# cvsource.net
KiCad netlist of a schematic drawn in EAGLE
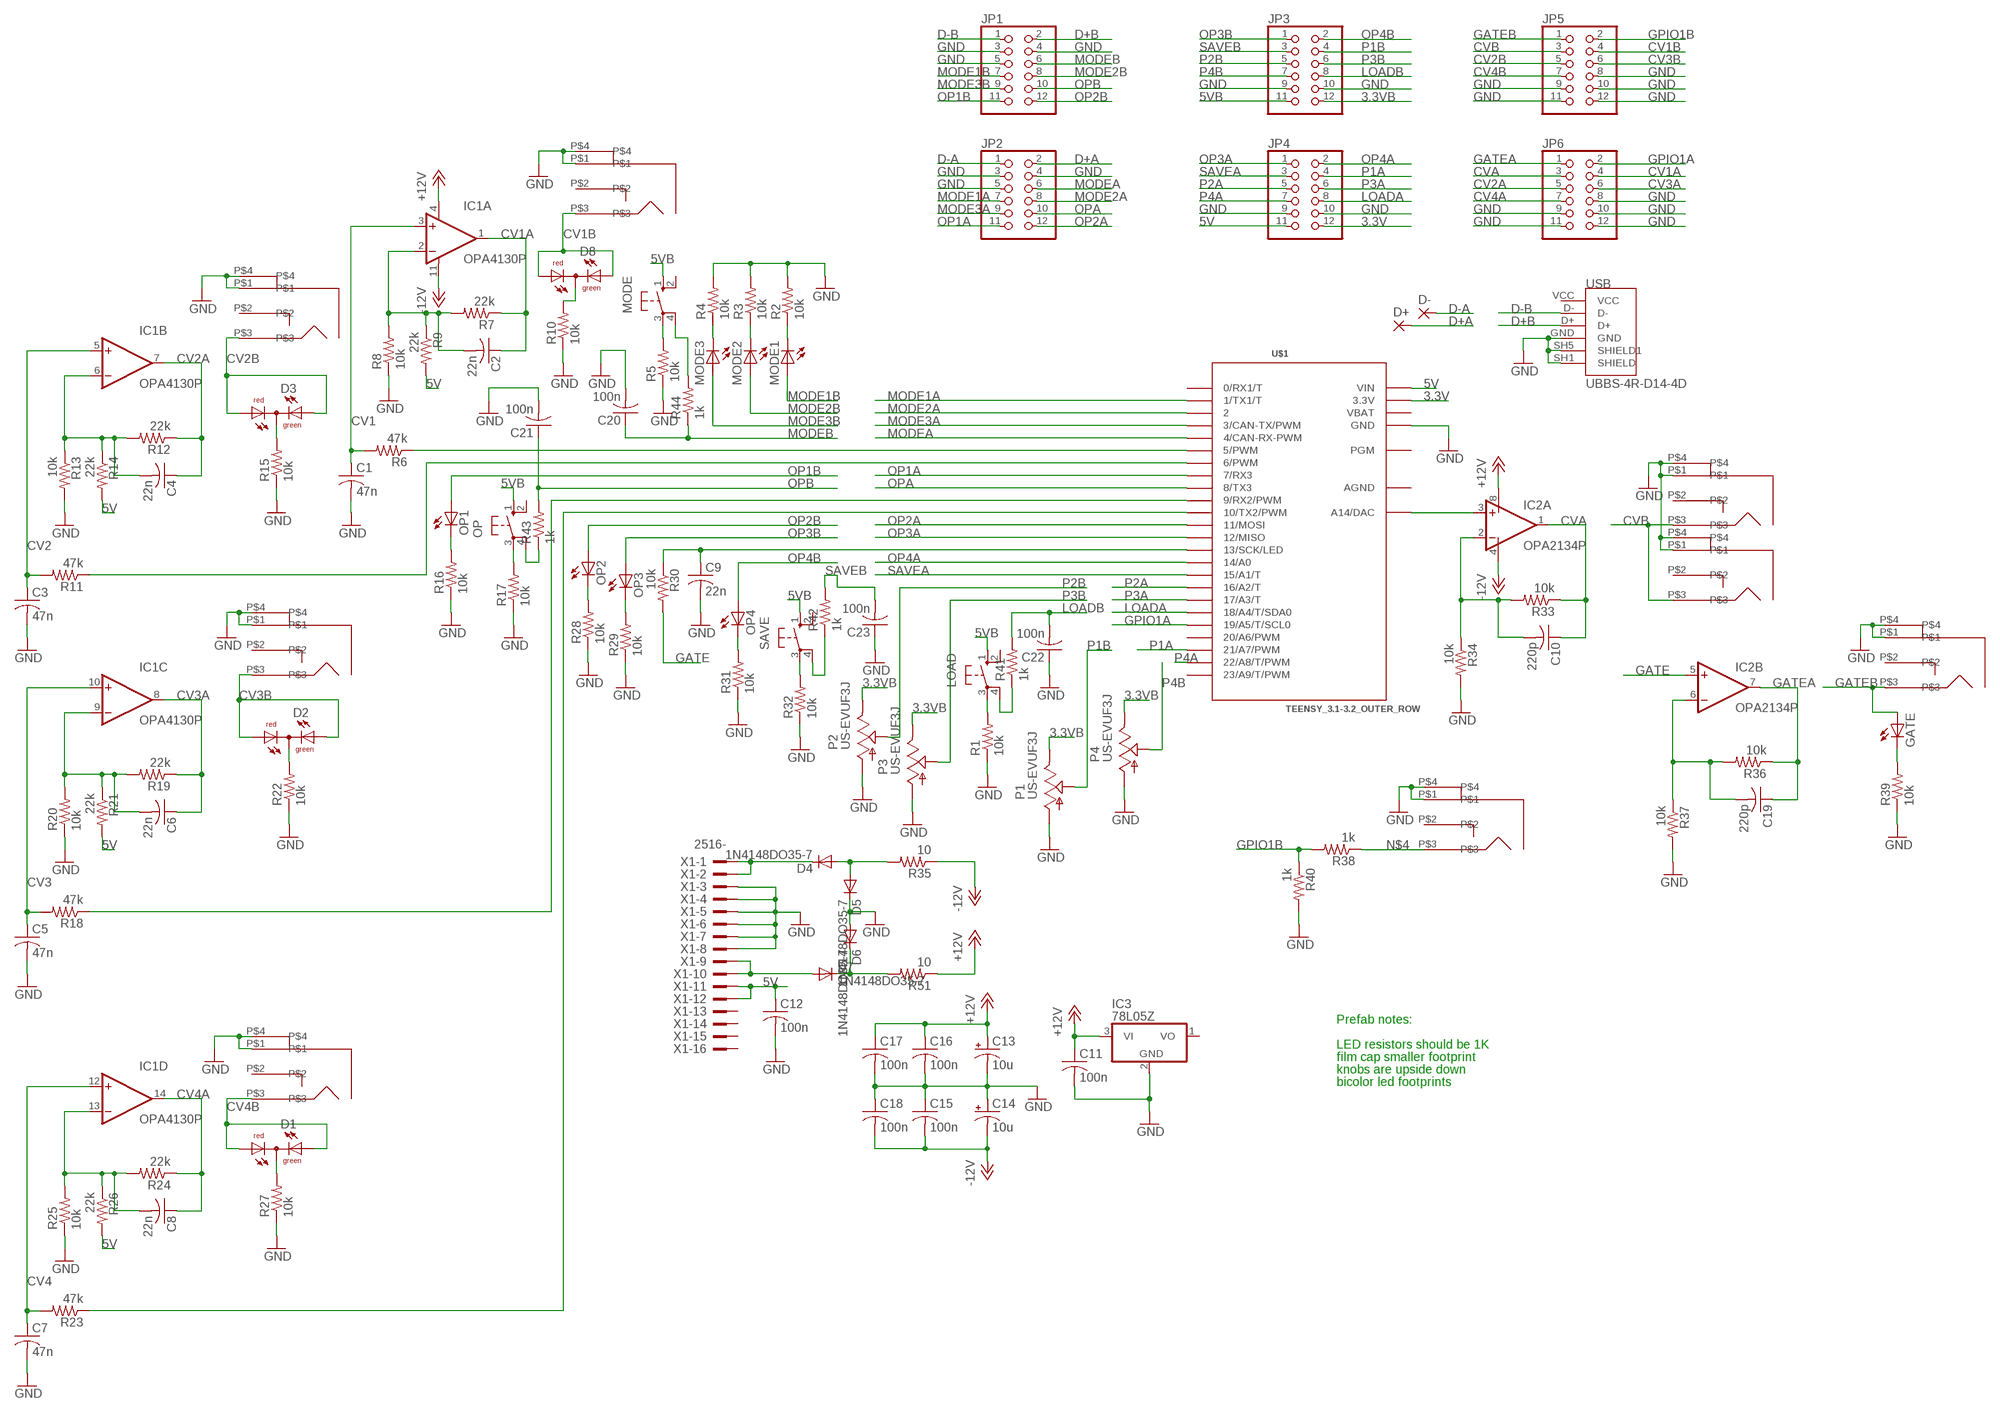
[diagram p0: schematic, sheet 1]

(export (version "E")
  (design (tool "Eeschema 10.0.6"))
  (components
    (comp (ref "C1")
      (value "47n")
      (footprint "eagle-import:C075-032X103")
      (libsource (lib "eagle-import") (part "C-US075-032X103"))
    )
    (comp (ref "C2")
      (value "22n")
      (footprint "eagle-import:C075-032X103")
      (libsource (lib "eagle-import") (part "C-US075-032X103"))
    )
    (comp (ref "C3")
      (value "47n")
      (footprint "eagle-import:C075-032X103")
      (libsource (lib "eagle-import") (part "C-US075-032X103"))
    )
    (comp (ref "C4")
      (value "22n")
      (footprint "eagle-import:C075-032X103")
      (libsource (lib "eagle-import") (part "C-US075-032X103"))
    )
    (comp (ref "C5")
      (value "47n")
      (footprint "eagle-import:C075-032X103")
      (libsource (lib "eagle-import") (part "C-US075-032X103"))
    )
    (comp (ref "C6")
      (value "22n")
      (footprint "eagle-import:C075-032X103")
      (libsource (lib "eagle-import") (part "C-US075-032X103"))
    )
    (comp (ref "C7")
      (value "47n")
      (footprint "eagle-import:C075-032X103")
      (libsource (lib "eagle-import") (part "C-US075-032X103"))
    )
    (comp (ref "C8")
      (value "22n")
      (footprint "eagle-import:C075-032X103")
      (libsource (lib "eagle-import") (part "C-US075-032X103"))
    )
    (comp (ref "C9")
      (value "22n")
      (footprint "eagle-import:C075-032X103")
      (libsource (lib "eagle-import") (part "C-US075-032X103"))
    )
    (comp (ref "C10")
      (value "220p")
      (footprint "eagle-import:C075-032X103")
      (libsource (lib "eagle-import") (part "C-US075-032X103"))
    )
    (comp (ref "C11")
      (value "100n")
      (footprint "eagle-import:C075-032X103")
      (libsource (lib "eagle-import") (part "C-US075-032X103"))
    )
    (comp (ref "C12")
      (value "100n")
      (footprint "eagle-import:C075-032X103")
      (libsource (lib "eagle-import") (part "C-US075-032X103"))
    )
    (comp (ref "C13")
      (value "10u")
      (footprint "eagle-import:E5-10,5")
      (libsource (lib "eagle-import") (part "CPOL-USE5-10.5"))
    )
    (comp (ref "C14")
      (value "10u")
      (footprint "eagle-import:E5-10,5")
      (libsource (lib "eagle-import") (part "CPOL-USE5-10.5"))
    )
    (comp (ref "C15")
      (value "100n")
      (footprint "eagle-import:C075-032X103")
      (libsource (lib "eagle-import") (part "C-US075-032X103"))
    )
    (comp (ref "C16")
      (value "100n")
      (footprint "eagle-import:C075-032X103")
      (libsource (lib "eagle-import") (part "C-US075-032X103"))
    )
    (comp (ref "C17")
      (value "100n")
      (footprint "eagle-import:C075-032X103")
      (libsource (lib "eagle-import") (part "C-US075-032X103"))
    )
    (comp (ref "C18")
      (value "100n")
      (footprint "eagle-import:C075-032X103")
      (libsource (lib "eagle-import") (part "C-US075-032X103"))
    )
    (comp (ref "C19")
      (value "220p")
      (footprint "eagle-import:C075-032X103")
      (libsource (lib "eagle-import") (part "C-US075-032X103"))
    )
    (comp (ref "C20")
      (value "100n")
      (footprint "eagle-import:C075-032X103")
      (libsource (lib "eagle-import") (part "C-US075-032X103"))
    )
    (comp (ref "C21")
      (value "100n")
      (footprint "eagle-import:C075-032X103")
      (libsource (lib "eagle-import") (part "C-US075-032X103"))
    )
    (comp (ref "C22")
      (value "100n")
      (footprint "eagle-import:C075-032X103")
      (libsource (lib "eagle-import") (part "C-US075-032X103"))
    )
    (comp (ref "C23")
      (value "100n")
      (footprint "eagle-import:C075-032X103")
      (libsource (lib "eagle-import") (part "C-US075-032X103"))
    )
    (comp (ref "CVOUT")
      (value "PJ301BM")
      (footprint "eagle-import:PJ301BM")
      (libsource (lib "eagle-import") (part "PJ301BM"))
    )
    (comp (ref "CVOUT1")
      (value "PJ301BM")
      (footprint "eagle-import:PJ301BM")
      (libsource (lib "eagle-import") (part "PJ301BM"))
    )
    (comp (ref "CVOUT2")
      (value "PJ301BM")
      (footprint "eagle-import:PJ301BM")
      (libsource (lib "eagle-import") (part "PJ301BM"))
    )
    (comp (ref "CVOUT3")
      (value "PJ301BM")
      (footprint "eagle-import:PJ301BM")
      (libsource (lib "eagle-import") (part "PJ301BM"))
    )
    (comp (ref "CVOUT4")
      (value "PJ301BM")
      (footprint "eagle-import:PJ301BM")
      (libsource (lib "eagle-import") (part "PJ301BM"))
    )
    (comp (ref "CVOUT5")
      (value "PJ301BM")
      (footprint "eagle-import:PJ301BM")
      (libsource (lib "eagle-import") (part "PJ301BM"))
    )
    (comp (ref "CVOUT6")
      (value "PJ301BM")
      (footprint "eagle-import:PJ301BM")
      (libsource (lib "eagle-import") (part "PJ301BM"))
    )
    (comp (ref "CVOUT7")
      (value "PJ301BM")
      (footprint "eagle-import:PJ301BM")
      (libsource (lib "eagle-import") (part "PJ301BM"))
    )
    (comp (ref "D+")
      (value "2,0/0,9-R")
      (footprint "eagle-import:2,0_0,9-R")
      (libsource (lib "eagle-import") (part "2,0/0,9-R"))
    )
    (comp (ref "D-")
      (value "2,0/0,9-R")
      (footprint "eagle-import:2,0_0,9-R")
      (libsource (lib "eagle-import") (part "2,0/0,9-R"))
    )
    (comp (ref "D1")
      (value "DUOLED5MM")
      (footprint "eagle-import:DUOLED5MM")
      (libsource (lib "eagle-import") (part "DUOLED5MM"))
    )
    (comp (ref "D2")
      (value "DUOLED5MM")
      (footprint "eagle-import:DUOLED5MM")
      (libsource (lib "eagle-import") (part "DUOLED5MM"))
    )
    (comp (ref "D3")
      (value "DUOLED5MM")
      (footprint "eagle-import:DUOLED5MM")
      (libsource (lib "eagle-import") (part "DUOLED5MM"))
    )
    (comp (ref "D4")
      (value "1N4148DO35-7")
      (footprint "eagle-import:DO35-7")
      (libsource (lib "eagle-import") (part "1N4148DO35-7"))
    )
    (comp (ref "D5")
      (value "1N4148DO35-7")
      (footprint "eagle-import:DO35-7")
      (libsource (lib "eagle-import") (part "1N4148DO35-7"))
    )
    (comp (ref "D6")
      (value "1N4148DO35-7")
      (footprint "eagle-import:DO35-7")
      (libsource (lib "eagle-import") (part "1N4148DO35-7"))
    )
    (comp (ref "D7")
      (value "1N4148DO35-7")
      (footprint "eagle-import:DO35-7")
      (libsource (lib "eagle-import") (part "1N4148DO35-7"))
    )
    (comp (ref "D8")
      (value "DUOLED5MM")
      (footprint "eagle-import:DUOLED5MM")
      (libsource (lib "eagle-import") (part "DUOLED5MM"))
    )
    (comp (ref "GATE")
      (value "LED5MM")
      (footprint "eagle-import:LED5MM")
      (libsource (lib "eagle-import") (part "LED5MM"))
    )
    (comp (ref "IC1")
      (value "OPA4130P")
      (footprint "eagle-import:DIL14")
      (libsource (lib "eagle-import") (part "OPA4130P"))
    )
    (comp (ref "IC2")
      (value "OPA2134P")
      (footprint "eagle-import:DIL08")
      (libsource (lib "eagle-import") (part "OPA2134P"))
    )
    (comp (ref "IC3")
      (value "78L05Z")
      (footprint "eagle-import:TO92")
      (libsource (lib "eagle-import") (part "78ZL05"))
    )
    (comp (ref "JP1")
      (value "PINHD-2X6")
      (footprint "eagle-import:2X06")
      (libsource (lib "eagle-import") (part "PINHD-2X6"))
    )
    (comp (ref "JP2")
      (value "PINHD-2X6")
      (footprint "eagle-import:2X06")
      (libsource (lib "eagle-import") (part "PINHD-2X6"))
    )
    (comp (ref "JP3")
      (value "PINHD-2X6")
      (footprint "eagle-import:2X06")
      (libsource (lib "eagle-import") (part "PINHD-2X6"))
    )
    (comp (ref "JP4")
      (value "PINHD-2X6")
      (footprint "eagle-import:2X06")
      (libsource (lib "eagle-import") (part "PINHD-2X6"))
    )
    (comp (ref "JP5")
      (value "PINHD-2X6")
      (footprint "eagle-import:2X06")
      (libsource (lib "eagle-import") (part "PINHD-2X6"))
    )
    (comp (ref "JP6")
      (value "PINHD-2X6")
      (footprint "eagle-import:2X06")
      (libsource (lib "eagle-import") (part "PINHD-2X6"))
    )
    (comp (ref "LOAD")
      (value "40-XX")
      (footprint "eagle-import:B3F-40XX")
      (fields (field (name "MF") "OMRON COMPONENTS USA") (field (name "MPN") "B3F-4000"))
      (libsource (lib "eagle-import") (part "40-XX"))
    )
    (comp (ref "MODE")
      (value "40-XX")
      (footprint "eagle-import:B3F-40XX")
      (fields (field (name "MF") "OMRON COMPONENTS USA") (field (name "MPN") "B3F-4000"))
      (libsource (lib "eagle-import") (part "40-XX"))
    )
    (comp (ref "MODE1")
      (value "LED5MM")
      (footprint "eagle-import:LED5MM")
      (libsource (lib "eagle-import") (part "LED5MM"))
    )
    (comp (ref "MODE2")
      (value "LED5MM")
      (footprint "eagle-import:LED5MM")
      (libsource (lib "eagle-import") (part "LED5MM"))
    )
    (comp (ref "MODE3")
      (value "LED5MM")
      (footprint "eagle-import:LED5MM")
      (libsource (lib "eagle-import") (part "LED5MM"))
    )
    (comp (ref "OP")
      (value "40-XX")
      (footprint "eagle-import:B3F-40XX")
      (fields (field (name "MF") "OMRON COMPONENTS USA") (field (name "MPN") "B3F-4000"))
      (libsource (lib "eagle-import") (part "40-XX"))
    )
    (comp (ref "OP1")
      (value "LED5MM")
      (footprint "eagle-import:LED5MM")
      (libsource (lib "eagle-import") (part "LED5MM"))
    )
    (comp (ref "OP2")
      (value "LED5MM")
      (footprint "eagle-import:LED5MM")
      (libsource (lib "eagle-import") (part "LED5MM"))
    )
    (comp (ref "OP3")
      (value "LED5MM")
      (footprint "eagle-import:LED5MM")
      (libsource (lib "eagle-import") (part "LED5MM"))
    )
    (comp (ref "OP4")
      (value "LED5MM")
      (footprint "eagle-import:LED5MM")
      (libsource (lib "eagle-import") (part "LED5MM"))
    )
    (comp (ref "P1")
      (value "US-EVUF3J")
      (footprint "eagle-import:EVUFXJ")
      (libsource (lib "eagle-import") (part "US-EVUF3J"))
    )
    (comp (ref "P2")
      (value "US-EVUF3J")
      (footprint "eagle-import:EVUFXJ")
      (libsource (lib "eagle-import") (part "US-EVUF3J"))
    )
    (comp (ref "P3")
      (value "US-EVUF3J")
      (footprint "eagle-import:EVUFXJ")
      (libsource (lib "eagle-import") (part "US-EVUF3J"))
    )
    (comp (ref "P4")
      (value "US-EVUF3J")
      (footprint "eagle-import:EVUFXJ")
      (libsource (lib "eagle-import") (part "US-EVUF3J"))
    )
    (comp (ref "R1")
      (value "10k")
      (footprint "eagle-import:0207_2V")
      (libsource (lib "eagle-import") (part "R-US_0207/2V"))
    )
    (comp (ref "R2")
      (value "10k")
      (footprint "eagle-import:0207_2V")
      (libsource (lib "eagle-import") (part "R-US_0207/2V"))
    )
    (comp (ref "R3")
      (value "10k")
      (footprint "eagle-import:0207_2V")
      (libsource (lib "eagle-import") (part "R-US_0207/2V"))
    )
    (comp (ref "R4")
      (value "10k")
      (footprint "eagle-import:0207_2V")
      (libsource (lib "eagle-import") (part "R-US_0207/2V"))
    )
    (comp (ref "R5")
      (value "10k")
      (footprint "eagle-import:0207_2V")
      (libsource (lib "eagle-import") (part "R-US_0207/2V"))
    )
    (comp (ref "R6")
      (value "47k")
      (footprint "eagle-import:0207_2V")
      (libsource (lib "eagle-import") (part "R-US_0207/2V"))
    )
    (comp (ref "R7")
      (value "22k")
      (footprint "eagle-import:0207_2V")
      (libsource (lib "eagle-import") (part "R-US_0207/2V"))
    )
    (comp (ref "R8")
      (value "10k")
      (footprint "eagle-import:0207_2V")
      (libsource (lib "eagle-import") (part "R-US_0207/2V"))
    )
    (comp (ref "R9")
      (value "22k")
      (footprint "eagle-import:0207_2V")
      (libsource (lib "eagle-import") (part "R-US_0207/2V"))
    )
    (comp (ref "R10")
      (value "10k")
      (footprint "eagle-import:0207_2V")
      (libsource (lib "eagle-import") (part "R-US_0207/2V"))
    )
    (comp (ref "R11")
      (value "47k")
      (footprint "eagle-import:0207_2V")
      (libsource (lib "eagle-import") (part "R-US_0207/2V"))
    )
    (comp (ref "R12")
      (value "22k")
      (footprint "eagle-import:0207_2V")
      (libsource (lib "eagle-import") (part "R-US_0207/2V"))
    )
    (comp (ref "R13")
      (value "10k")
      (footprint "eagle-import:0207_2V")
      (libsource (lib "eagle-import") (part "R-US_0207/2V"))
    )
    (comp (ref "R14")
      (value "22k")
      (footprint "eagle-import:0207_2V")
      (libsource (lib "eagle-import") (part "R-US_0207/2V"))
    )
    (comp (ref "R15")
      (value "10k")
      (footprint "eagle-import:0207_2V")
      (libsource (lib "eagle-import") (part "R-US_0207/2V"))
    )
    (comp (ref "R16")
      (value "10k")
      (footprint "eagle-import:0207_2V")
      (libsource (lib "eagle-import") (part "R-US_0207/2V"))
    )
    (comp (ref "R17")
      (value "10k")
      (footprint "eagle-import:0207_2V")
      (libsource (lib "eagle-import") (part "R-US_0207/2V"))
    )
    (comp (ref "R18")
      (value "47k")
      (footprint "eagle-import:0207_2V")
      (libsource (lib "eagle-import") (part "R-US_0207/2V"))
    )
    (comp (ref "R19")
      (value "22k")
      (footprint "eagle-import:0207_2V")
      (libsource (lib "eagle-import") (part "R-US_0207/2V"))
    )
    (comp (ref "R20")
      (value "10k")
      (footprint "eagle-import:0207_2V")
      (libsource (lib "eagle-import") (part "R-US_0207/2V"))
    )
    (comp (ref "R21")
      (value "22k")
      (footprint "eagle-import:0207_2V")
      (libsource (lib "eagle-import") (part "R-US_0207/2V"))
    )
    (comp (ref "R22")
      (value "10k")
      (footprint "eagle-import:0207_2V")
      (libsource (lib "eagle-import") (part "R-US_0207/2V"))
    )
    (comp (ref "R23")
      (value "47k")
      (footprint "eagle-import:0207_2V")
      (libsource (lib "eagle-import") (part "R-US_0207/2V"))
    )
    (comp (ref "R24")
      (value "22k")
      (footprint "eagle-import:0207_2V")
      (libsource (lib "eagle-import") (part "R-US_0207/2V"))
    )
    (comp (ref "R25")
      (value "10k")
      (footprint "eagle-import:0207_2V")
      (libsource (lib "eagle-import") (part "R-US_0207/2V"))
    )
    (comp (ref "R26")
      (value "22k")
      (footprint "eagle-import:0207_2V")
      (libsource (lib "eagle-import") (part "R-US_0207/2V"))
    )
    (comp (ref "R27")
      (value "10k")
      (footprint "eagle-import:0207_2V")
      (libsource (lib "eagle-import") (part "R-US_0207/2V"))
    )
    (comp (ref "R28")
      (value "10k")
      (footprint "eagle-import:0207_2V")
      (libsource (lib "eagle-import") (part "R-US_0207/2V"))
    )
    (comp (ref "R29")
      (value "10k")
      (footprint "eagle-import:0207_2V")
      (libsource (lib "eagle-import") (part "R-US_0207/2V"))
    )
    (comp (ref "R30")
      (value "10k")
      (footprint "eagle-import:0207_2V")
      (libsource (lib "eagle-import") (part "R-US_0207/2V"))
    )
    (comp (ref "R31")
      (value "10k")
      (footprint "eagle-import:0207_2V")
      (libsource (lib "eagle-import") (part "R-US_0207/2V"))
    )
    (comp (ref "R32")
      (value "10k")
      (footprint "eagle-import:0207_2V")
      (libsource (lib "eagle-import") (part "R-US_0207/2V"))
    )
    (comp (ref "R33")
      (value "10k")
      (footprint "eagle-import:0207_2V")
      (libsource (lib "eagle-import") (part "R-US_0207/2V"))
    )
    (comp (ref "R34")
      (value "10k")
      (footprint "eagle-import:0207_2V")
      (libsource (lib "eagle-import") (part "R-US_0207/2V"))
    )
    (comp (ref "R35")
      (value "10")
      (footprint "eagle-import:0207_2V")
      (libsource (lib "eagle-import") (part "R-US_0207/2V"))
    )
    (comp (ref "R36")
      (value "10k")
      (footprint "eagle-import:0207_2V")
      (libsource (lib "eagle-import") (part "R-US_0207/2V"))
    )
    (comp (ref "R37")
      (value "10k")
      (footprint "eagle-import:0207_2V")
      (libsource (lib "eagle-import") (part "R-US_0207/2V"))
    )
    (comp (ref "R38")
      (value "1k")
      (footprint "eagle-import:0207_2V")
      (libsource (lib "eagle-import") (part "R-US_0207/2V"))
    )
    (comp (ref "R39")
      (value "10k")
      (footprint "eagle-import:0207_2V")
      (libsource (lib "eagle-import") (part "R-US_0207/2V"))
    )
    (comp (ref "R40")
      (value "1k")
      (footprint "eagle-import:0207_2V")
      (libsource (lib "eagle-import") (part "R-US_0207/2V"))
    )
    (comp (ref "R41")
      (value "1k")
      (footprint "eagle-import:0207_2V")
      (libsource (lib "eagle-import") (part "R-US_0207/2V"))
    )
    (comp (ref "R42")
      (value "1k")
      (footprint "eagle-import:0207_2V")
      (libsource (lib "eagle-import") (part "R-US_0207/2V"))
    )
    (comp (ref "R43")
      (value "1k")
      (footprint "eagle-import:0207_2V")
      (libsource (lib "eagle-import") (part "R-US_0207/2V"))
    )
    (comp (ref "R44")
      (value "1k")
      (footprint "eagle-import:0207_2V")
      (libsource (lib "eagle-import") (part "R-US_0207/2V"))
    )
    (comp (ref "R51")
      (value "10")
      (footprint "eagle-import:0207_2V")
      (libsource (lib "eagle-import") (part "R-US_0207/2V"))
    )
    (comp (ref "SAVE")
      (value "40-XX")
      (footprint "eagle-import:B3F-40XX")
      (fields (field (name "MF") "OMRON COMPONENTS USA") (field (name "MPN") "B3F-4000"))
      (libsource (lib "eagle-import") (part "40-XX"))
    )
    (comp (ref "U$1")
      (value "TEENSY_3.1-3.2_OUTER_ROW")
      (footprint "eagle-import:TEENSY_3.0-3.2&LC_OUTER_ROW")
      (libsource (lib "eagle-import") (part "TEENSY_3.1-3.2_OUTER_ROW"))
    )
    (comp (ref "USB")
      (value "UBBS-4R-D14-4D")
      (footprint "eagle-import:JST_UBBS-4R-D14-4D")
      (fields (field (name "MF") "JST"))
      (libsource (lib "eagle-import") (part "UBBS-4R-D14-4D"))
    )
    (comp (ref "X1")
      (value "2516-")
      (footprint "eagle-import:PAK100_2500-16")
      (libsource (lib "eagle-import") (part "2516-"))
    )
  )
  (nets
    (net (code "1") (name "+12V") (class "Default")
      (node (ref "C11") (pin "1") (pinfunction "1_1") (pintype "passive"))
      (node (ref "C13") (pin "+") (pinfunction "+_+") (pintype "passive"))
      (node (ref "C16") (pin "1") (pinfunction "1_1") (pintype "passive"))
      (node (ref "C17") (pin "1") (pinfunction "1_1") (pintype "passive"))
      (node (ref "IC1") (pin "4") (pinfunction "V+_4") (pintype "power_in"))
      (node (ref "IC2") (pin "8") (pinfunction "V+_8") (pintype "power_in"))
      (node (ref "IC3") (pin "3") (pinfunction "VI_3") (pintype "input"))
      (node (ref "R51") (pin "1") (pinfunction "1_1") (pintype "passive"))
    )
    (net (code "2") (name "-12V") (class "Default")
      (node (ref "C14") (pin "-") (pinfunction "-_-") (pintype "passive"))
      (node (ref "C15") (pin "2") (pinfunction "2_2") (pintype "passive"))
      (node (ref "C18") (pin "2") (pinfunction "2_2") (pintype "passive"))
      (node (ref "IC1") (pin "11") (pinfunction "V-_11") (pintype "power_in"))
      (node (ref "IC2") (pin "4") (pinfunction "V-_4") (pintype "power_in"))
      (node (ref "R35") (pin "1") (pinfunction "1_1") (pintype "passive"))
    )
    (net (code "3") (name "/3.3V") (class "Default")
      (node (ref "JP4") (pin "12") (pinfunction "12_12") (pintype "passive"))
      (node (ref "U$1") (pin "3.3V") (pinfunction "3.3V_3.3V") (pintype "power_in"))
      (node (ref "U$1") (pin "3.3V1") (pinfunction "3.3V_3.3V1") (pintype "power_in"))
    )
    (net (code "4") (name "/3.3VB") (class "Default")
      (node (ref "JP3") (pin "12") (pinfunction "12_12") (pintype "passive"))
      (node (ref "P1") (pin "3") (pinfunction "E_3") (pintype "passive"))
      (node (ref "P2") (pin "3") (pinfunction "E_3") (pintype "passive"))
      (node (ref "P3") (pin "3") (pinfunction "E_3") (pintype "passive"))
      (node (ref "P4") (pin "3") (pinfunction "E_3") (pintype "passive"))
    )
    (net (code "5") (name "/5V") (class "Default")
      (node (ref "C12") (pin "1") (pinfunction "1_1") (pintype "passive"))
      (node (ref "JP4") (pin "11") (pinfunction "11_11") (pintype "passive"))
      (node (ref "R14") (pin "2") (pinfunction "2_2") (pintype "passive"))
      (node (ref "R21") (pin "2") (pinfunction "2_2") (pintype "passive"))
      (node (ref "R26") (pin "2") (pinfunction "2_2") (pintype "passive"))
      (node (ref "R9") (pin "2") (pinfunction "2_2") (pintype "passive"))
      (node (ref "U$1") (pin "VIN") (pinfunction "VIN_VIN") (pintype "power_in"))
      (node (ref "X1") (pin "11") (pinfunction "KL_11") (pintype "passive"))
      (node (ref "X1") (pin "12") (pinfunction "KL_12") (pintype "passive"))
    )
    (net (code "6") (name "/5VB") (class "Default")
      (node (ref "JP3") (pin "11") (pinfunction "11_11") (pintype "passive"))
      (node (ref "LOAD") (pin "1") (pinfunction "S_1") (pintype "passive"))
      (node (ref "MODE") (pin "1") (pinfunction "S_1") (pintype "passive"))
      (node (ref "OP") (pin "1") (pinfunction "S_1") (pintype "passive"))
      (node (ref "SAVE") (pin "1") (pinfunction "S_1") (pintype "passive"))
    )
    (net (code "7") (name "/AGND") (class "Default")
      (node (ref "U$1") (pin "AGND") (pinfunction "AGND_AGND") (pintype "power_in"))
    )
    (net (code "8") (name "/CV1") (class "Default")
      (node (ref "C1") (pin "1") (pinfunction "1_1") (pintype "passive"))
      (node (ref "IC1") (pin "3") (pinfunction "+IN_3") (pintype "input"))
      (node (ref "R6") (pin "2") (pinfunction "2_2") (pintype "passive"))
    )
    (net (code "9") (name "/CV1A") (class "Default")
      (node (ref "C2") (pin "1") (pinfunction "1_1") (pintype "passive"))
      (node (ref "IC1") (pin "1") (pinfunction "OUT_1") (pintype "output"))
      (node (ref "JP6") (pin "4") (pinfunction "4_4") (pintype "passive"))
      (node (ref "R7") (pin "1") (pinfunction "1_1") (pintype "passive"))
    )
    (net (code "10") (name "/CV1B") (class "Default")
      (node (ref "CVOUT1") (pin "P$3") (pinfunction "P$3_P$3") (pintype "bidirectional"))
      (node (ref "D8") (pin "AG") (pinfunction "AG_AG") (pintype "passive"))
      (node (ref "D8") (pin "AR") (pinfunction "AR_AR") (pintype "passive"))
      (node (ref "JP5") (pin "4") (pinfunction "4_4") (pintype "passive"))
    )
    (net (code "11") (name "/CV2") (class "Default")
      (node (ref "C3") (pin "1") (pinfunction "1_1") (pintype "passive"))
      (node (ref "IC1") (pin "5") (pinfunction "+IN_5") (pintype "input"))
      (node (ref "R11") (pin "2") (pinfunction "2_2") (pintype "passive"))
    )
    (net (code "12") (name "/CV2A") (class "Default")
      (node (ref "C4") (pin "1") (pinfunction "1_1") (pintype "passive"))
      (node (ref "IC1") (pin "7") (pinfunction "OUT_7") (pintype "output"))
      (node (ref "JP6") (pin "5") (pinfunction "5_5") (pintype "passive"))
      (node (ref "R12") (pin "1") (pinfunction "1_1") (pintype "passive"))
    )
    (net (code "13") (name "/CV2B") (class "Default")
      (node (ref "CVOUT2") (pin "P$3") (pinfunction "P$3_P$3") (pintype "bidirectional"))
      (node (ref "D3") (pin "AG") (pinfunction "AG_AG") (pintype "passive"))
      (node (ref "D3") (pin "AR") (pinfunction "AR_AR") (pintype "passive"))
      (node (ref "JP5") (pin "5") (pinfunction "5_5") (pintype "passive"))
    )
    (net (code "14") (name "/CV3") (class "Default")
      (node (ref "C5") (pin "1") (pinfunction "1_1") (pintype "passive"))
      (node (ref "IC1") (pin "10") (pinfunction "+IN_10") (pintype "input"))
      (node (ref "R18") (pin "2") (pinfunction "2_2") (pintype "passive"))
    )
    (net (code "15") (name "/CV3A") (class "Default")
      (node (ref "C6") (pin "1") (pinfunction "1_1") (pintype "passive"))
      (node (ref "IC1") (pin "8") (pinfunction "OUT_8") (pintype "output"))
      (node (ref "JP6") (pin "6") (pinfunction "6_6") (pintype "passive"))
      (node (ref "R19") (pin "1") (pinfunction "1_1") (pintype "passive"))
    )
    (net (code "16") (name "/CV3B") (class "Default")
      (node (ref "CVOUT3") (pin "P$3") (pinfunction "P$3_P$3") (pintype "bidirectional"))
      (node (ref "D2") (pin "AG") (pinfunction "AG_AG") (pintype "passive"))
      (node (ref "D2") (pin "AR") (pinfunction "AR_AR") (pintype "passive"))
      (node (ref "JP5") (pin "6") (pinfunction "6_6") (pintype "passive"))
    )
    (net (code "17") (name "/CV4") (class "Default")
      (node (ref "C7") (pin "1") (pinfunction "1_1") (pintype "passive"))
      (node (ref "IC1") (pin "12") (pinfunction "+IN_12") (pintype "input"))
      (node (ref "R23") (pin "2") (pinfunction "2_2") (pintype "passive"))
    )
    (net (code "18") (name "/CV4A") (class "Default")
      (node (ref "C8") (pin "1") (pinfunction "1_1") (pintype "passive"))
      (node (ref "IC1") (pin "14") (pinfunction "OUT_14") (pintype "output"))
      (node (ref "JP6") (pin "7") (pinfunction "7_7") (pintype "passive"))
      (node (ref "R24") (pin "1") (pinfunction "1_1") (pintype "passive"))
    )
    (net (code "19") (name "/CV4B") (class "Default")
      (node (ref "CVOUT4") (pin "P$3") (pinfunction "P$3_P$3") (pintype "bidirectional"))
      (node (ref "D1") (pin "AG") (pinfunction "AG_AG") (pintype "passive"))
      (node (ref "D1") (pin "AR") (pinfunction "AR_AR") (pintype "passive"))
      (node (ref "JP5") (pin "7") (pinfunction "7_7") (pintype "passive"))
    )
    (net (code "20") (name "/CVA") (class "Default")
      (node (ref "C10") (pin "1") (pinfunction "1_1") (pintype "passive"))
      (node (ref "IC2") (pin "1") (pinfunction "OUT_1") (pintype "output"))
      (node (ref "JP6") (pin "3") (pinfunction "3_3") (pintype "passive"))
      (node (ref "R33") (pin "1") (pinfunction "1_1") (pintype "passive"))
    )
    (net (code "21") (name "/CVB") (class "Default")
      (node (ref "CVOUT") (pin "P$3") (pinfunction "P$3_P$3") (pintype "bidirectional"))
      (node (ref "CVOUT6") (pin "P$3") (pinfunction "P$3_P$3") (pintype "bidirectional"))
      (node (ref "JP5") (pin "3") (pinfunction "3_3") (pintype "passive"))
    )
    (net (code "22") (name "/D+A") (class "Default")
      (node (ref "D+") (pin "1") (pinfunction "P_1") (pintype "passive"))
      (node (ref "JP2") (pin "2") (pinfunction "2_2") (pintype "passive"))
    )
    (net (code "23") (name "/D+B") (class "Default")
      (node (ref "JP1") (pin "2") (pinfunction "2_2") (pintype "passive"))
      (node (ref "USB") (pin "D+") (pinfunction "D+_D+") (pintype "passive"))
    )
    (net (code "24") (name "/D-A") (class "Default")
      (node (ref "D-") (pin "1") (pinfunction "P_1") (pintype "passive"))
      (node (ref "JP2") (pin "1") (pinfunction "1_1") (pintype "passive"))
    )
    (net (code "25") (name "/D-B") (class "Default")
      (node (ref "JP1") (pin "1") (pinfunction "1_1") (pintype "passive"))
      (node (ref "USB") (pin "D-") (pinfunction "D-_D-") (pintype "passive"))
    )
    (net (code "26") (name "/GATE") (class "Default")
      (node (ref "IC2") (pin "5") (pinfunction "+IN_5") (pintype "input"))
      (node (ref "R30") (pin "2") (pinfunction "2_2") (pintype "passive"))
    )
    (net (code "27") (name "/GATEA") (class "Default")
      (node (ref "C19") (pin "1") (pinfunction "1_1") (pintype "passive"))
      (node (ref "IC2") (pin "7") (pinfunction "OUT_7") (pintype "output"))
      (node (ref "JP6") (pin "1") (pinfunction "1_1") (pintype "passive"))
      (node (ref "R36") (pin "1") (pinfunction "1_1") (pintype "passive"))
    )
    (net (code "28") (name "/GATEB") (class "Default")
      (node (ref "CVOUT5") (pin "P$3") (pinfunction "P$3_P$3") (pintype "bidirectional"))
      (node (ref "GATE") (pin "A") (pinfunction "A_A") (pintype "passive"))
      (node (ref "JP5") (pin "1") (pinfunction "1_1") (pintype "passive"))
    )
    (net (code "29") (name "/GPIO1A") (class "Default")
      (node (ref "JP6") (pin "2") (pinfunction "2_2") (pintype "passive"))
      (node (ref "U$1") (pin "19/A5") (pinfunction "19/A5/T/SCL0_19/A5") (pintype "bidirectional"))
    )
    (net (code "30") (name "/GPIO1B") (class "Default")
      (node (ref "JP5") (pin "2") (pinfunction "2_2") (pintype "passive"))
      (node (ref "R38") (pin "2") (pinfunction "2_2") (pintype "passive"))
      (node (ref "R40") (pin "1") (pinfunction "1_1") (pintype "passive"))
    )
    (net (code "31") (name "/LOADA") (class "Default")
      (node (ref "JP4") (pin "8") (pinfunction "8_8") (pintype "passive"))
      (node (ref "U$1") (pin "18/A4") (pinfunction "18/A4/T/SDA0_18/A4") (pintype "bidirectional"))
    )
    (net (code "32") (name "/LOADB") (class "Default")
      (node (ref "C22") (pin "2") (pinfunction "2_2") (pintype "passive"))
      (node (ref "JP3") (pin "8") (pinfunction "8_8") (pintype "passive"))
      (node (ref "R41") (pin "2") (pinfunction "2_2") (pintype "passive"))
    )
    (net (code "33") (name "/MODE1A") (class "Default")
      (node (ref "JP2") (pin "7") (pinfunction "7_7") (pintype "passive"))
      (node (ref "U$1") (pin "1") (pinfunction "1/TX1/T_1") (pintype "bidirectional"))
    )
    (net (code "34") (name "/MODE1B") (class "Default")
      (node (ref "JP1") (pin "7") (pinfunction "7_7") (pintype "passive"))
      (node (ref "MODE1") (pin "A") (pinfunction "A_A") (pintype "passive"))
    )
    (net (code "35") (name "/MODE2A") (class "Default")
      (node (ref "JP2") (pin "8") (pinfunction "8_8") (pintype "passive"))
      (node (ref "U$1") (pin "2") (pinfunction "2_2") (pintype "bidirectional"))
    )
    (net (code "36") (name "/MODE2B") (class "Default")
      (node (ref "JP1") (pin "8") (pinfunction "8_8") (pintype "passive"))
      (node (ref "MODE2") (pin "A") (pinfunction "A_A") (pintype "passive"))
    )
    (net (code "37") (name "/MODE3A") (class "Default")
      (node (ref "JP2") (pin "9") (pinfunction "9_9") (pintype "passive"))
      (node (ref "U$1") (pin "3") (pinfunction "3/CAN-TX/PWM_3") (pintype "bidirectional"))
    )
    (net (code "38") (name "/MODE3B") (class "Default")
      (node (ref "JP1") (pin "9") (pinfunction "9_9") (pintype "passive"))
      (node (ref "MODE3") (pin "A") (pinfunction "A_A") (pintype "passive"))
    )
    (net (code "39") (name "/MODEA") (class "Default")
      (node (ref "JP2") (pin "6") (pinfunction "6_6") (pintype "passive"))
      (node (ref "U$1") (pin "4") (pinfunction "4/CAN-RX-PWM_4") (pintype "bidirectional"))
    )
    (net (code "40") (name "/MODEB") (class "Default")
      (node (ref "C20") (pin "1") (pinfunction "1_1") (pintype "passive"))
      (node (ref "JP1") (pin "6") (pinfunction "6_6") (pintype "passive"))
      (node (ref "R44") (pin "1") (pinfunction "1_1") (pintype "passive"))
    )
    (net (code "41") (name "/N$4") (class "Default")
      (node (ref "CVOUT7") (pin "P$3") (pinfunction "P$3_P$3") (pintype "bidirectional"))
      (node (ref "R38") (pin "1") (pinfunction "1_1") (pintype "passive"))
    )
    (net (code "42") (name "/OP1A") (class "Default")
      (node (ref "JP2") (pin "11") (pinfunction "11_11") (pintype "passive"))
      (node (ref "U$1") (pin "7") (pinfunction "7/RX3_7") (pintype "bidirectional"))
    )
    (net (code "43") (name "/OP1B") (class "Default")
      (node (ref "JP1") (pin "11") (pinfunction "11_11") (pintype "passive"))
      (node (ref "OP1") (pin "A") (pinfunction "A_A") (pintype "passive"))
    )
    (net (code "44") (name "/OP2A") (class "Default")
      (node (ref "JP2") (pin "12") (pinfunction "12_12") (pintype "passive"))
      (node (ref "U$1") (pin "11") (pinfunction "11/MOSI_11") (pintype "bidirectional"))
    )
    (net (code "45") (name "/OP2B") (class "Default")
      (node (ref "JP1") (pin "12") (pinfunction "12_12") (pintype "passive"))
      (node (ref "OP2") (pin "A") (pinfunction "A_A") (pintype "passive"))
    )
    (net (code "46") (name "/OP3A") (class "Default")
      (node (ref "JP4") (pin "1") (pinfunction "1_1") (pintype "passive"))
      (node (ref "U$1") (pin "12") (pinfunction "12/MISO_12") (pintype "bidirectional"))
    )
    (net (code "47") (name "/OP3B") (class "Default")
      (node (ref "JP3") (pin "1") (pinfunction "1_1") (pintype "passive"))
      (node (ref "OP3") (pin "A") (pinfunction "A_A") (pintype "passive"))
    )
    (net (code "48") (name "/OP4A") (class "Default")
      (node (ref "JP4") (pin "2") (pinfunction "2_2") (pintype "passive"))
      (node (ref "U$1") (pin "14/A0") (pinfunction "14/A0_14/A0") (pintype "bidirectional"))
    )
    (net (code "49") (name "/OP4B") (class "Default")
      (node (ref "JP3") (pin "2") (pinfunction "2_2") (pintype "passive"))
      (node (ref "OP4") (pin "A") (pinfunction "A_A") (pintype "passive"))
    )
    (net (code "50") (name "/OPA") (class "Default")
      (node (ref "JP2") (pin "10") (pinfunction "10_10") (pintype "passive"))
      (node (ref "U$1") (pin "8") (pinfunction "8/TX3_8") (pintype "bidirectional"))
    )
    (net (code "51") (name "/OPB") (class "Default")
      (node (ref "C21") (pin "1") (pinfunction "1_1") (pintype "passive"))
      (node (ref "JP1") (pin "10") (pinfunction "10_10") (pintype "passive"))
      (node (ref "R43") (pin "2") (pinfunction "2_2") (pintype "passive"))
    )
    (net (code "52") (name "/P1A") (class "Default")
      (node (ref "JP4") (pin "4") (pinfunction "4_4") (pintype "passive"))
      (node (ref "U$1") (pin "21/A7") (pinfunction "21/A7/PWM_21/A7") (pintype "bidirectional"))
    )
    (net (code "53") (name "/P1B") (class "Default")
      (node (ref "JP3") (pin "4") (pinfunction "4_4") (pintype "passive"))
      (node (ref "P1") (pin "2") (pinfunction "S_2") (pintype "passive"))
    )
    (net (code "54") (name "/P2A") (class "Default")
      (node (ref "JP4") (pin "5") (pinfunction "5_5") (pintype "passive"))
      (node (ref "U$1") (pin "16/A2") (pinfunction "16/A2/T_16/A2") (pintype "bidirectional"))
    )
    (net (code "55") (name "/P2B") (class "Default")
      (node (ref "JP3") (pin "5") (pinfunction "5_5") (pintype "passive"))
      (node (ref "P2") (pin "2") (pinfunction "S_2") (pintype "passive"))
    )
    (net (code "56") (name "/P3A") (class "Default")
      (node (ref "JP4") (pin "6") (pinfunction "6_6") (pintype "passive"))
      (node (ref "U$1") (pin "17/A3") (pinfunction "17/A3/T_17/A3") (pintype "bidirectional"))
    )
    (net (code "57") (name "/P3B") (class "Default")
      (node (ref "JP3") (pin "6") (pinfunction "6_6") (pintype "passive"))
      (node (ref "P3") (pin "2") (pinfunction "S_2") (pintype "passive"))
    )
    (net (code "58") (name "/P4A") (class "Default")
      (node (ref "JP4") (pin "7") (pinfunction "7_7") (pintype "passive"))
      (node (ref "U$1") (pin "22/A8") (pinfunction "22/A8/T/PWM_22/A8") (pintype "bidirectional"))
    )
    (net (code "59") (name "/P4B") (class "Default")
      (node (ref "JP3") (pin "7") (pinfunction "7_7") (pintype "passive"))
      (node (ref "P4") (pin "2") (pinfunction "S_2") (pintype "passive"))
    )
    (net (code "60") (name "/SAVEA") (class "Default")
      (node (ref "JP4") (pin "3") (pinfunction "3_3") (pintype "passive"))
      (node (ref "U$1") (pin "15/A1") (pinfunction "15/A1/T_15/A1") (pintype "bidirectional"))
    )
    (net (code "61") (name "/SAVEB") (class "Default")
      (node (ref "C23") (pin "2") (pinfunction "2_2") (pintype "passive"))
      (node (ref "JP3") (pin "3") (pinfunction "3_3") (pintype "passive"))
      (node (ref "R42") (pin "2") (pinfunction "2_2") (pintype "passive"))
    )
    (net (code "62") (name "/VBAT") (class "Default")
      (node (ref "U$1") (pin "VBAT") (pinfunction "VBAT_VBAT") (pintype "power_in"))
    )
    (net (code "63") (name "GND") (class "Default")
      (node (ref "C1") (pin "2") (pinfunction "2_2") (pintype "passive"))
      (node (ref "C11") (pin "2") (pinfunction "2_2") (pintype "passive"))
      (node (ref "C12") (pin "2") (pinfunction "2_2") (pintype "passive"))
      (node (ref "C13") (pin "-") (pinfunction "-_-") (pintype "passive"))
      (node (ref "C14") (pin "+") (pinfunction "+_+") (pintype "passive"))
      (node (ref "C15") (pin "1") (pinfunction "1_1") (pintype "passive"))
      (node (ref "C16") (pin "2") (pinfunction "2_2") (pintype "passive"))
      (node (ref "C17") (pin "2") (pinfunction "2_2") (pintype "passive"))
      (node (ref "C18") (pin "1") (pinfunction "1_1") (pintype "passive"))
      (node (ref "C20") (pin "2") (pinfunction "2_2") (pintype "passive"))
      (node (ref "C21") (pin "2") (pinfunction "2_2") (pintype "passive"))
      (node (ref "C22") (pin "1") (pinfunction "1_1") (pintype "passive"))
      (node (ref "C23") (pin "1") (pinfunction "1_1") (pintype "passive"))
      (node (ref "C3") (pin "2") (pinfunction "2_2") (pintype "passive"))
      (node (ref "C5") (pin "2") (pinfunction "2_2") (pintype "passive"))
      (node (ref "C7") (pin "2") (pinfunction "2_2") (pintype "passive"))
      (node (ref "C9") (pin "2") (pinfunction "2_2") (pintype "passive"))
      (node (ref "CVOUT") (pin "P$1") (pinfunction "P$1_P$1") (pintype "bidirectional"))
      (node (ref "CVOUT") (pin "P$4") (pinfunction "P$4_P$4") (pintype "bidirectional"))
      (node (ref "CVOUT1") (pin "P$1") (pinfunction "P$1_P$1") (pintype "bidirectional"))
      (node (ref "CVOUT1") (pin "P$4") (pinfunction "P$4_P$4") (pintype "bidirectional"))
      (node (ref "CVOUT2") (pin "P$1") (pinfunction "P$1_P$1") (pintype "bidirectional"))
      (node (ref "CVOUT2") (pin "P$4") (pinfunction "P$4_P$4") (pintype "bidirectional"))
      (node (ref "CVOUT3") (pin "P$1") (pinfunction "P$1_P$1") (pintype "bidirectional"))
      (node (ref "CVOUT3") (pin "P$4") (pinfunction "P$4_P$4") (pintype "bidirectional"))
      (node (ref "CVOUT4") (pin "P$1") (pinfunction "P$1_P$1") (pintype "bidirectional"))
      (node (ref "CVOUT4") (pin "P$4") (pinfunction "P$4_P$4") (pintype "bidirectional"))
      (node (ref "CVOUT5") (pin "P$1") (pinfunction "P$1_P$1") (pintype "bidirectional"))
      (node (ref "CVOUT5") (pin "P$4") (pinfunction "P$4_P$4") (pintype "bidirectional"))
      (node (ref "CVOUT6") (pin "P$1") (pinfunction "P$1_P$1") (pintype "bidirectional"))
      (node (ref "CVOUT6") (pin "P$4") (pinfunction "P$4_P$4") (pintype "bidirectional"))
      (node (ref "CVOUT7") (pin "P$1") (pinfunction "P$1_P$1") (pintype "bidirectional"))
      (node (ref "CVOUT7") (pin "P$4") (pinfunction "P$4_P$4") (pintype "bidirectional"))
      (node (ref "D5") (pin "C") (pinfunction "C_C") (pintype "passive"))
      (node (ref "D6") (pin "A") (pinfunction "A_A") (pintype "passive"))
      (node (ref "IC3") (pin "2") (pinfunction "GND_2") (pintype "passive"))
      (node (ref "JP1") (pin "3") (pinfunction "3_3") (pintype "passive"))
      (node (ref "JP1") (pin "4") (pinfunction "4_4") (pintype "passive"))
      (node (ref "JP1") (pin "5") (pinfunction "5_5") (pintype "passive"))
      (node (ref "JP2") (pin "3") (pinfunction "3_3") (pintype "passive"))
      (node (ref "JP2") (pin "4") (pinfunction "4_4") (pintype "passive"))
      (node (ref "JP2") (pin "5") (pinfunction "5_5") (pintype "passive"))
      (node (ref "JP3") (pin "10") (pinfunction "10_10") (pintype "passive"))
      (node (ref "JP3") (pin "9") (pinfunction "9_9") (pintype "passive"))
      (node (ref "JP4") (pin "10") (pinfunction "10_10") (pintype "passive"))
      (node (ref "JP4") (pin "9") (pinfunction "9_9") (pintype "passive"))
      (node (ref "JP5") (pin "10") (pinfunction "10_10") (pintype "passive"))
      (node (ref "JP5") (pin "11") (pinfunction "11_11") (pintype "passive"))
      (node (ref "JP5") (pin "12") (pinfunction "12_12") (pintype "passive"))
      (node (ref "JP5") (pin "8") (pinfunction "8_8") (pintype "passive"))
      (node (ref "JP5") (pin "9") (pinfunction "9_9") (pintype "passive"))
      (node (ref "JP6") (pin "10") (pinfunction "10_10") (pintype "passive"))
      (node (ref "JP6") (pin "11") (pinfunction "11_11") (pintype "passive"))
      (node (ref "JP6") (pin "12") (pinfunction "12_12") (pintype "passive"))
      (node (ref "JP6") (pin "8") (pinfunction "8_8") (pintype "passive"))
      (node (ref "JP6") (pin "9") (pinfunction "9_9") (pintype "passive"))
      (node (ref "P1") (pin "1") (pinfunction "A_1") (pintype "passive"))
      (node (ref "P2") (pin "1") (pinfunction "A_1") (pintype "passive"))
      (node (ref "P3") (pin "1") (pinfunction "A_1") (pintype "passive"))
      (node (ref "P4") (pin "1") (pinfunction "A_1") (pintype "passive"))
      (node (ref "R1") (pin "1") (pinfunction "1_1") (pintype "passive"))
      (node (ref "R10") (pin "1") (pinfunction "1_1") (pintype "passive"))
      (node (ref "R13") (pin "2") (pinfunction "2_2") (pintype "passive"))
      (node (ref "R15") (pin "1") (pinfunction "1_1") (pintype "passive"))
      (node (ref "R16") (pin "1") (pinfunction "1_1") (pintype "passive"))
      (node (ref "R17") (pin "1") (pinfunction "1_1") (pintype "passive"))
      (node (ref "R2") (pin "2") (pinfunction "2_2") (pintype "passive"))
      (node (ref "R20") (pin "1") (pinfunction "1_1") (pintype "passive"))
      (node (ref "R22") (pin "1") (pinfunction "1_1") (pintype "passive"))
      (node (ref "R25") (pin "1") (pinfunction "1_1") (pintype "passive"))
      (node (ref "R27") (pin "1") (pinfunction "1_1") (pintype "passive"))
      (node (ref "R28") (pin "1") (pinfunction "1_1") (pintype "passive"))
      (node (ref "R29") (pin "1") (pinfunction "1_1") (pintype "passive"))
      (node (ref "R3") (pin "2") (pinfunction "2_2") (pintype "passive"))
      (node (ref "R31") (pin "1") (pinfunction "1_1") (pintype "passive"))
      (node (ref "R32") (pin "1") (pinfunction "1_1") (pintype "passive"))
      (node (ref "R34") (pin "2") (pinfunction "2_2") (pintype "passive"))
      (node (ref "R37") (pin "2") (pinfunction "2_2") (pintype "passive"))
      (node (ref "R39") (pin "1") (pinfunction "1_1") (pintype "passive"))
      (node (ref "R4") (pin "2") (pinfunction "2_2") (pintype "passive"))
      (node (ref "R40") (pin "2") (pinfunction "2_2") (pintype "passive"))
      (node (ref "R5") (pin "1") (pinfunction "1_1") (pintype "passive"))
      (node (ref "R8") (pin "1") (pinfunction "1_1") (pintype "passive"))
      (node (ref "U$1") (pin "GND") (pinfunction "GND_GND") (pintype "power_in"))
      (node (ref "U$1") (pin "GND1") (pinfunction "GND_GND1") (pintype "power_in"))
      (node (ref "USB") (pin "GND") (pinfunction "GND_GND") (pintype "passive"))
      (node (ref "USB") (pin "SH1") (pinfunction "SHIELD_SH1") (pintype "passive"))
      (node (ref "USB") (pin "SH5") (pinfunction "SHIELD1_SH5") (pintype "bidirectional"))
      (node (ref "X1") (pin "3") (pinfunction "KL_3") (pintype "passive"))
      (node (ref "X1") (pin "4") (pinfunction "KL_4") (pintype "passive"))
      (node (ref "X1") (pin "5") (pinfunction "KL_5") (pintype "passive"))
      (node (ref "X1") (pin "6") (pinfunction "KL_6") (pintype "passive"))
      (node (ref "X1") (pin "7") (pinfunction "KL_7") (pintype "passive"))
      (node (ref "X1") (pin "8") (pinfunction "KL_8") (pintype "passive"))
    )
    (net (code "64") (name "Net-(D1-C)") (class "Default")
      (node (ref "D1") (pin "K") (pinfunction "C_K") (pintype "passive"))
      (node (ref "R27") (pin "2") (pinfunction "2_2") (pintype "passive"))
    )
    (net (code "65") (name "Net-(D2-C)") (class "Default")
      (node (ref "D2") (pin "K") (pinfunction "C_K") (pintype "passive"))
      (node (ref "R22") (pin "2") (pinfunction "2_2") (pintype "passive"))
    )
    (net (code "66") (name "Net-(D3-C)") (class "Default")
      (node (ref "D3") (pin "K") (pinfunction "C_K") (pintype "passive"))
      (node (ref "R15") (pin "2") (pinfunction "2_2") (pintype "passive"))
    )
    (net (code "67") (name "Net-(D4-PadA)") (class "Default")
      (node (ref "D4") (pin "A") (pinfunction "A_A") (pintype "passive"))
      (node (ref "D5") (pin "A") (pinfunction "A_A") (pintype "passive"))
      (node (ref "R35") (pin "2") (pinfunction "2_2") (pintype "passive"))
    )
    (net (code "68") (name "Net-(D6-PadC)") (class "Default")
      (node (ref "D6") (pin "C") (pinfunction "C_C") (pintype "passive"))
      (node (ref "D7") (pin "C") (pinfunction "C_C") (pintype "passive"))
      (node (ref "R51") (pin "2") (pinfunction "2_2") (pintype "passive"))
    )
    (net (code "69") (name "Net-(D8-C)") (class "Default")
      (node (ref "D8") (pin "K") (pinfunction "C_K") (pintype "passive"))
      (node (ref "R10") (pin "2") (pinfunction "2_2") (pintype "passive"))
    )
    (net (code "70") (name "Net-(GATE-C)") (class "Default")
      (node (ref "GATE") (pin "K") (pinfunction "C_K") (pintype "passive"))
      (node (ref "R39") (pin "2") (pinfunction "2_2") (pintype "passive"))
    )
    (net (code "71") (name "Net-(IC1A--IN)") (class "Default")
      (node (ref "C2") (pin "2") (pinfunction "2_2") (pintype "passive"))
      (node (ref "IC1") (pin "2") (pinfunction "-IN_2") (pintype "input"))
      (node (ref "R7") (pin "2") (pinfunction "2_2") (pintype "passive"))
      (node (ref "R8") (pin "2") (pinfunction "2_2") (pintype "passive"))
      (node (ref "R9") (pin "1") (pinfunction "1_1") (pintype "passive"))
    )
    (net (code "72") (name "Net-(IC1B--IN)") (class "Default")
      (node (ref "C4") (pin "2") (pinfunction "2_2") (pintype "passive"))
      (node (ref "IC1") (pin "6") (pinfunction "-IN_6") (pintype "input"))
      (node (ref "R12") (pin "2") (pinfunction "2_2") (pintype "passive"))
      (node (ref "R13") (pin "1") (pinfunction "1_1") (pintype "passive"))
      (node (ref "R14") (pin "1") (pinfunction "1_1") (pintype "passive"))
    )
    (net (code "73") (name "Net-(IC1C--IN)") (class "Default")
      (node (ref "C6") (pin "2") (pinfunction "2_2") (pintype "passive"))
      (node (ref "IC1") (pin "9") (pinfunction "-IN_9") (pintype "input"))
      (node (ref "R19") (pin "2") (pinfunction "2_2") (pintype "passive"))
      (node (ref "R20") (pin "2") (pinfunction "2_2") (pintype "passive"))
      (node (ref "R21") (pin "1") (pinfunction "1_1") (pintype "passive"))
    )
    (net (code "74") (name "Net-(IC1D--IN)") (class "Default")
      (node (ref "C8") (pin "2") (pinfunction "2_2") (pintype "passive"))
      (node (ref "IC1") (pin "13") (pinfunction "-IN_13") (pintype "input"))
      (node (ref "R24") (pin "2") (pinfunction "2_2") (pintype "passive"))
      (node (ref "R25") (pin "2") (pinfunction "2_2") (pintype "passive"))
      (node (ref "R26") (pin "1") (pinfunction "1_1") (pintype "passive"))
    )
    (net (code "75") (name "Net-(IC2A-+IN)") (class "Default")
      (node (ref "IC2") (pin "3") (pinfunction "+IN_3") (pintype "input"))
      (node (ref "U$1") (pin "RESET/DAC") (pinfunction "A14/DAC_RESET/DAC") (pintype "bidirectional"))
    )
    (net (code "76") (name "Net-(IC2A--IN)") (class "Default")
      (node (ref "C10") (pin "2") (pinfunction "2_2") (pintype "passive"))
      (node (ref "IC2") (pin "2") (pinfunction "-IN_2") (pintype "input"))
      (node (ref "R33") (pin "2") (pinfunction "2_2") (pintype "passive"))
      (node (ref "R34") (pin "1") (pinfunction "1_1") (pintype "passive"))
    )
    (net (code "77") (name "Net-(IC2B--IN)") (class "Default")
      (node (ref "C19") (pin "2") (pinfunction "2_2") (pintype "passive"))
      (node (ref "IC2") (pin "6") (pinfunction "-IN_6") (pintype "input"))
      (node (ref "R36") (pin "2") (pinfunction "2_2") (pintype "passive"))
      (node (ref "R37") (pin "1") (pinfunction "1_1") (pintype "passive"))
    )
    (net (code "78") (name "Net-(LOAD-P)") (class "Default")
      (node (ref "LOAD") (pin "3") (pinfunction "P_3") (pintype "passive"))
      (node (ref "R1") (pin "2") (pinfunction "2_2") (pintype "passive"))
    )
    (net (code "79") (name "Net-(LOAD-P1)") (class "Default")
      (node (ref "LOAD") (pin "4") (pinfunction "P1_4") (pintype "passive"))
      (node (ref "R41") (pin "1") (pinfunction "1_1") (pintype "passive"))
    )
    (net (code "80") (name "Net-(MODE-P)") (class "Default")
      (node (ref "MODE") (pin "3") (pinfunction "P_3") (pintype "passive"))
      (node (ref "R5") (pin "2") (pinfunction "2_2") (pintype "passive"))
    )
    (net (code "81") (name "Net-(MODE-P1)") (class "Default")
      (node (ref "MODE") (pin "4") (pinfunction "P1_4") (pintype "passive"))
      (node (ref "R44") (pin "2") (pinfunction "2_2") (pintype "passive"))
    )
    (net (code "82") (name "Net-(MODE1-C)") (class "Default")
      (node (ref "MODE1") (pin "K") (pinfunction "C_K") (pintype "passive"))
      (node (ref "R2") (pin "1") (pinfunction "1_1") (pintype "passive"))
    )
    (net (code "83") (name "Net-(MODE2-C)") (class "Default")
      (node (ref "MODE2") (pin "K") (pinfunction "C_K") (pintype "passive"))
      (node (ref "R3") (pin "1") (pinfunction "1_1") (pintype "passive"))
    )
    (net (code "84") (name "Net-(MODE3-C)") (class "Default")
      (node (ref "MODE3") (pin "K") (pinfunction "C_K") (pintype "passive"))
      (node (ref "R4") (pin "1") (pinfunction "1_1") (pintype "passive"))
    )
    (net (code "85") (name "Net-(OP-P)") (class "Default")
      (node (ref "OP") (pin "3") (pinfunction "P_3") (pintype "passive"))
      (node (ref "R17") (pin "2") (pinfunction "2_2") (pintype "passive"))
    )
    (net (code "86") (name "Net-(OP-P1)") (class "Default")
      (node (ref "OP") (pin "4") (pinfunction "P1_4") (pintype "passive"))
      (node (ref "R43") (pin "1") (pinfunction "1_1") (pintype "passive"))
    )
    (net (code "87") (name "Net-(OP1-C)") (class "Default")
      (node (ref "OP1") (pin "K") (pinfunction "C_K") (pintype "passive"))
      (node (ref "R16") (pin "2") (pinfunction "2_2") (pintype "passive"))
    )
    (net (code "88") (name "Net-(OP2-C)") (class "Default")
      (node (ref "OP2") (pin "K") (pinfunction "C_K") (pintype "passive"))
      (node (ref "R28") (pin "2") (pinfunction "2_2") (pintype "passive"))
    )
    (net (code "89") (name "Net-(OP3-C)") (class "Default")
      (node (ref "OP3") (pin "K") (pinfunction "C_K") (pintype "passive"))
      (node (ref "R29") (pin "2") (pinfunction "2_2") (pintype "passive"))
    )
    (net (code "90") (name "Net-(OP4-C)") (class "Default")
      (node (ref "OP4") (pin "K") (pinfunction "C_K") (pintype "passive"))
      (node (ref "R31") (pin "2") (pinfunction "2_2") (pintype "passive"))
    )
    (net (code "91") (name "Net-(SAVE-P)") (class "Default")
      (node (ref "R32") (pin "2") (pinfunction "2_2") (pintype "passive"))
      (node (ref "SAVE") (pin "3") (pinfunction "P_3") (pintype "passive"))
    )
    (net (code "92") (name "Net-(SAVE-P1)") (class "Default")
      (node (ref "R42") (pin "1") (pinfunction "1_1") (pintype "passive"))
      (node (ref "SAVE") (pin "4") (pinfunction "P1_4") (pintype "passive"))
    )
    (net (code "93") (name "Net-(U$1-5{slash}PWM)") (class "Default")
      (node (ref "R6") (pin "1") (pinfunction "1_1") (pintype "passive"))
      (node (ref "U$1") (pin "5") (pinfunction "5/PWM_5") (pintype "bidirectional"))
    )
    (net (code "94") (name "Net-(U$1-6{slash}PWM)") (class "Default")
      (node (ref "R11") (pin "1") (pinfunction "1_1") (pintype "passive"))
      (node (ref "U$1") (pin "6") (pinfunction "6/PWM_6") (pintype "bidirectional"))
    )
    (net (code "95") (name "Net-(U$1-9{slash}RX2{slash}PWM)") (class "Default")
      (node (ref "R18") (pin "1") (pinfunction "1_1") (pintype "passive"))
      (node (ref "U$1") (pin "9") (pinfunction "9/RX2/PWM_9") (pintype "bidirectional"))
    )
    (net (code "96") (name "Net-(U$1-10{slash}TX2{slash}PWM)") (class "Default")
      (node (ref "R23") (pin "1") (pinfunction "1_1") (pintype "passive"))
      (node (ref "U$1") (pin "10") (pinfunction "10/TX2/PWM_10") (pintype "bidirectional"))
    )
    (net (code "97") (name "Net-(U$1-13{slash}SCK{slash}LED)") (class "Default")
      (node (ref "C9") (pin "1") (pinfunction "1_1") (pintype "passive"))
      (node (ref "R30") (pin "1") (pinfunction "1_1") (pintype "passive"))
      (node (ref "U$1") (pin "13") (pinfunction "13/SCK/LED_13") (pintype "bidirectional"))
    )
    (net (code "98") (name "Net-(X1A-KL)") (class "Default")
      (node (ref "D4") (pin "C") (pinfunction "C_C") (pintype "passive"))
      (node (ref "X1") (pin "1") (pinfunction "KL_1") (pintype "passive"))
      (node (ref "X1") (pin "2") (pinfunction "KL_2") (pintype "passive"))
    )
    (net (code "99") (name "Net-(X1B-KL)") (class "Default")
      (node (ref "D7") (pin "A") (pinfunction "A_A") (pintype "passive"))
      (node (ref "X1") (pin "10") (pinfunction "KL_10") (pintype "passive"))
      (node (ref "X1") (pin "9") (pinfunction "KL_9") (pintype "passive"))
    )
    (net (code "100") (name "unconnected-(CVOUT-PadP$2)") (class "Default")
      (node (ref "CVOUT") (pin "P$2") (pinfunction "P$2_P$2") (pintype "bidirectional"))
    )
    (net (code "101") (name "unconnected-(CVOUT1-PadP$2)") (class "Default")
      (node (ref "CVOUT1") (pin "P$2") (pinfunction "P$2_P$2") (pintype "bidirectional"))
    )
    (net (code "102") (name "unconnected-(CVOUT2-PadP$2)") (class "Default")
      (node (ref "CVOUT2") (pin "P$2") (pinfunction "P$2_P$2") (pintype "bidirectional"))
    )
    (net (code "103") (name "unconnected-(CVOUT3-PadP$2)") (class "Default")
      (node (ref "CVOUT3") (pin "P$2") (pinfunction "P$2_P$2") (pintype "bidirectional"))
    )
    (net (code "104") (name "unconnected-(CVOUT4-PadP$2)") (class "Default")
      (node (ref "CVOUT4") (pin "P$2") (pinfunction "P$2_P$2") (pintype "bidirectional"))
    )
    (net (code "105") (name "unconnected-(CVOUT5-PadP$2)") (class "Default")
      (node (ref "CVOUT5") (pin "P$2") (pinfunction "P$2_P$2") (pintype "bidirectional"))
    )
    (net (code "106") (name "unconnected-(CVOUT6-PadP$2)") (class "Default")
      (node (ref "CVOUT6") (pin "P$2") (pinfunction "P$2_P$2") (pintype "bidirectional"))
    )
    (net (code "107") (name "unconnected-(CVOUT7-PadP$2)") (class "Default")
      (node (ref "CVOUT7") (pin "P$2") (pinfunction "P$2_P$2") (pintype "bidirectional"))
    )
    (net (code "108") (name "unconnected-(IC3-VO-Pad1)") (class "Default")
      (node (ref "IC3") (pin "1") (pinfunction "VO_1") (pintype "passive"))
    )
    (net (code "109") (name "unconnected-(LOAD-S1-Pad2)") (class "Default")
      (node (ref "LOAD") (pin "2") (pinfunction "S1_2") (pintype "passive"))
    )
    (net (code "110") (name "unconnected-(MODE-S1-Pad2)") (class "Default")
      (node (ref "MODE") (pin "2") (pinfunction "S1_2") (pintype "passive"))
    )
    (net (code "111") (name "unconnected-(OP-S1-Pad2)") (class "Default")
      (node (ref "OP") (pin "2") (pinfunction "S1_2") (pintype "passive"))
    )
    (net (code "112") (name "unconnected-(SAVE-S1-Pad2)") (class "Default")
      (node (ref "SAVE") (pin "2") (pinfunction "S1_2") (pintype "passive"))
    )
    (net (code "113") (name "unconnected-(U$1-0{slash}RX1{slash}T-Pad0)") (class "Default")
      (node (ref "U$1") (pin "0") (pinfunction "0/RX1/T_0") (pintype "bidirectional"))
    )
    (net (code "114") (name "unconnected-(U$1-20{slash}A6{slash}PWM-Pad20{slash}A6)") (class "Default")
      (node (ref "U$1") (pin "20/A6") (pinfunction "20/A6/PWM_20/A6") (pintype "bidirectional"))
    )
    (net (code "115") (name "unconnected-(U$1-23{slash}A9{slash}T{slash}PWM-Pad23{slash}A9)") (class "Default")
      (node (ref "U$1") (pin "23/A9") (pinfunction "23/A9/T/PWM_23/A9") (pintype "bidirectional"))
    )
    (net (code "116") (name "unconnected-(U$1-PadPGM)") (class "Default")
      (node (ref "U$1") (pin "PGM") (pinfunction "PGM_PGM") (pintype "bidirectional"))
    )
    (net (code "117") (name "unconnected-(USB-PadVCC)") (class "Default")
      (node (ref "USB") (pin "VCC") (pinfunction "VCC_VCC") (pintype "passive"))
    )
    (net (code "118") (name "unconnected-(X1E-KL-Pad13)") (class "Default")
      (node (ref "X1") (pin "13") (pinfunction "KL_13") (pintype "passive"))
    )
    (net (code "119") (name "unconnected-(X1F-KL-Pad14)") (class "Default")
      (node (ref "X1") (pin "14") (pinfunction "KL_14") (pintype "passive"))
    )
    (net (code "120") (name "unconnected-(X1G-KL-Pad15)") (class "Default")
      (node (ref "X1") (pin "15") (pinfunction "KL_15") (pintype "passive"))
    )
    (net (code "121") (name "unconnected-(X1H-KL-Pad16)") (class "Default")
      (node (ref "X1") (pin "16") (pinfunction "KL_16") (pintype "passive"))
    )
  )
)
